# Humus_ethernet_dip_v1.net
KiCad netlist of a schematic drawn in EAGLE
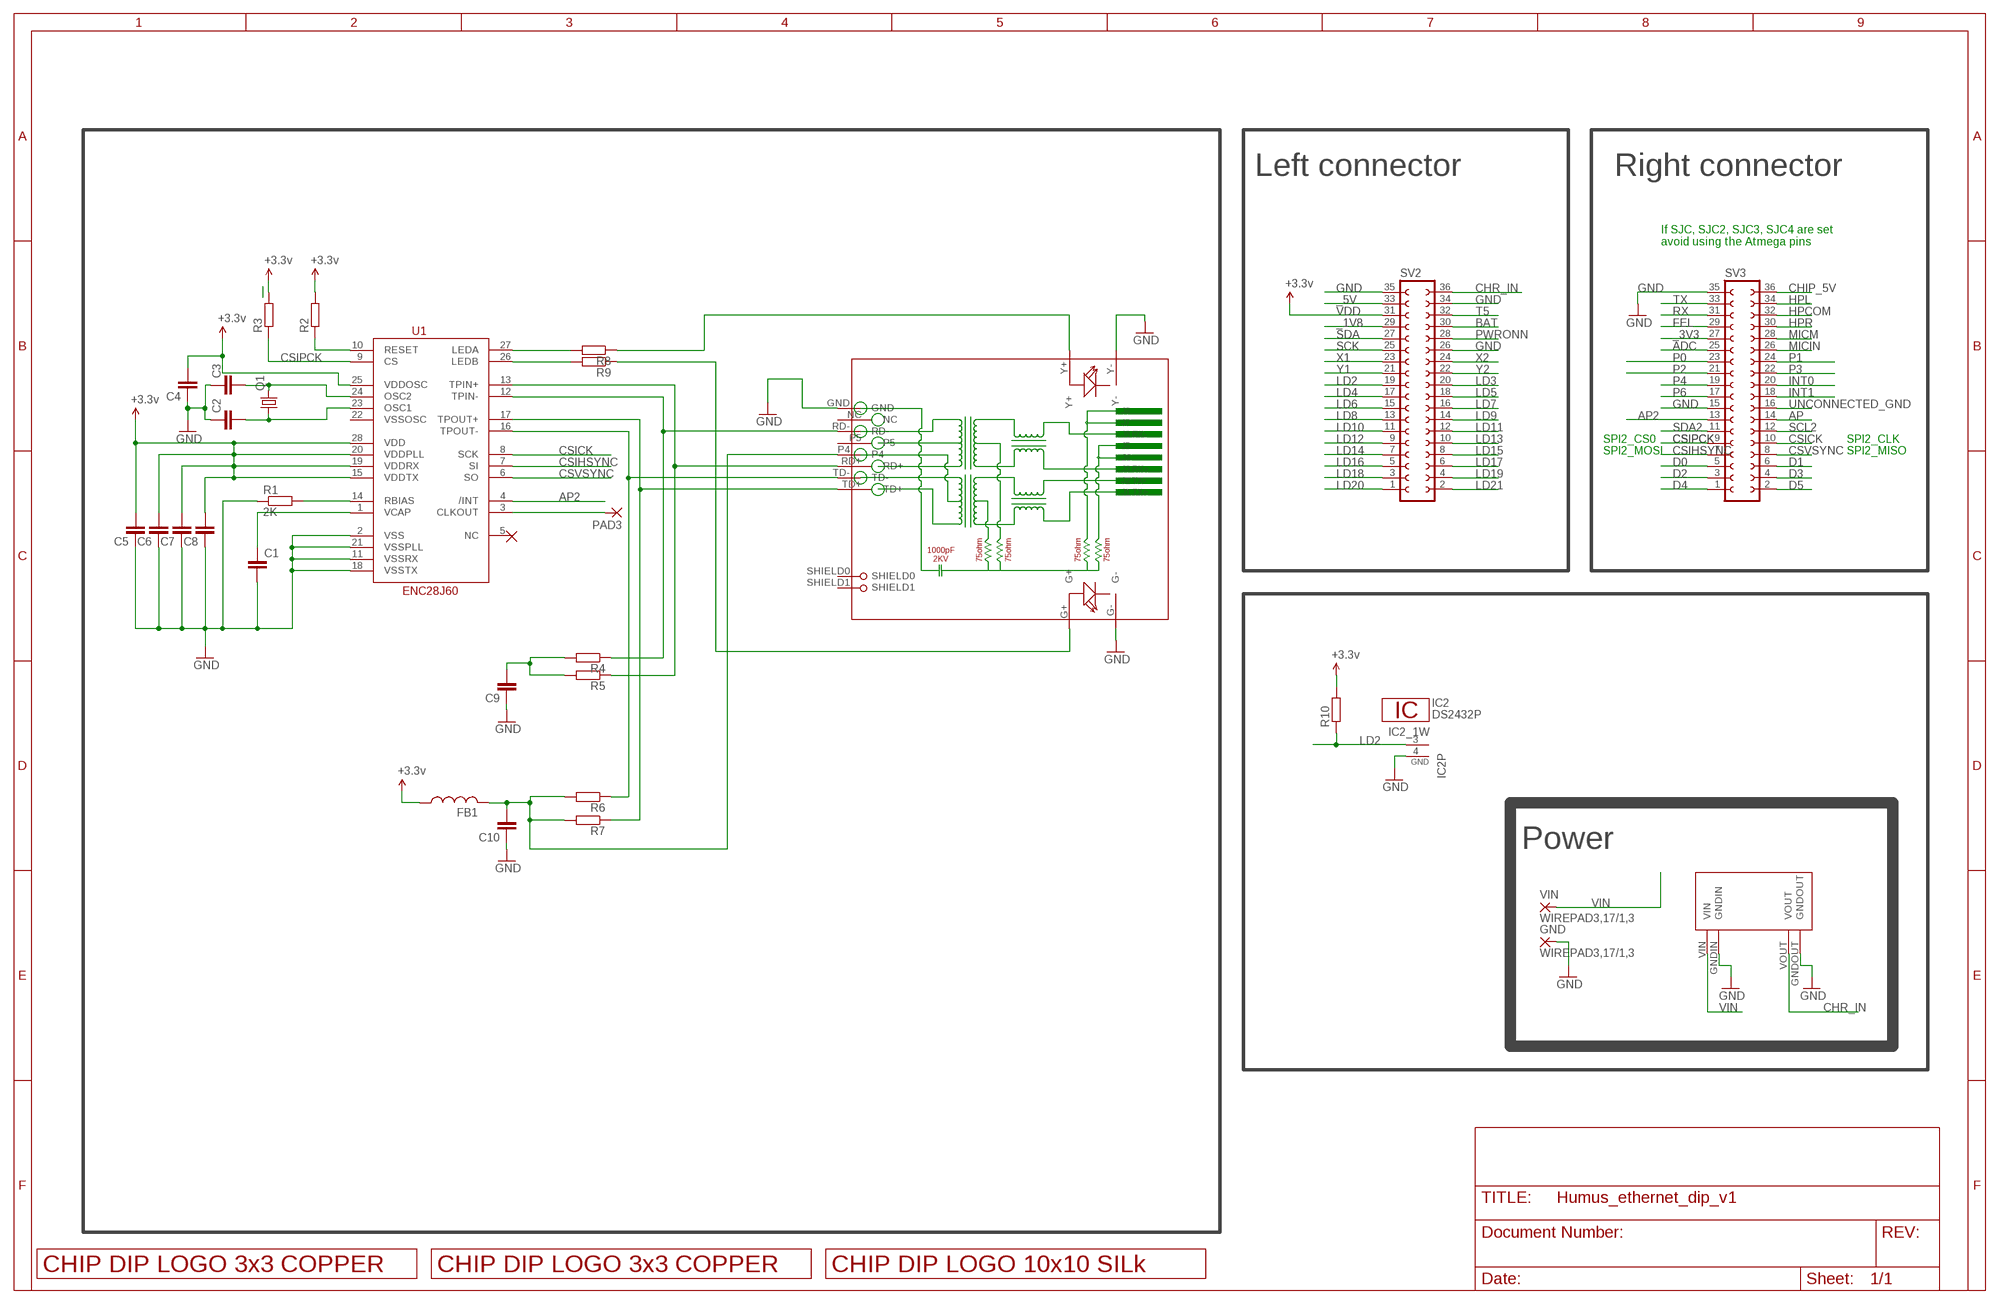
[diagram p0: schematic, sheet 1]

(export (version "E")
  (design (tool "Eeschema 10.0.6"))
  (components
    (comp (ref "C1")
      (value "C-EUC0805")
      (footprint "eagle-import:C0805")
      (libsource (lib "eagle-import") (part "C-EUC0805"))
    )
    (comp (ref "C2")
      (value "C-EUC0805")
      (footprint "eagle-import:C0805")
      (libsource (lib "eagle-import") (part "C-EUC0805"))
    )
    (comp (ref "C3")
      (value "C-EUC0805")
      (footprint "eagle-import:C0805")
      (libsource (lib "eagle-import") (part "C-EUC0805"))
    )
    (comp (ref "C4")
      (value "C-EUC0805")
      (footprint "eagle-import:C0805")
      (libsource (lib "eagle-import") (part "C-EUC0805"))
    )
    (comp (ref "C5")
      (value "C-EUC0805")
      (footprint "eagle-import:C0805")
      (libsource (lib "eagle-import") (part "C-EUC0805"))
    )
    (comp (ref "C6")
      (value "C-EUC0805")
      (footprint "eagle-import:C0805")
      (libsource (lib "eagle-import") (part "C-EUC0805"))
    )
    (comp (ref "C7")
      (value "C-EUC0805")
      (footprint "eagle-import:C0805")
      (libsource (lib "eagle-import") (part "C-EUC0805"))
    )
    (comp (ref "C8")
      (value "C-EUC0805")
      (footprint "eagle-import:C0805")
      (libsource (lib "eagle-import") (part "C-EUC0805"))
    )
    (comp (ref "C9")
      (value "C-EUC0805")
      (footprint "eagle-import:C0805")
      (libsource (lib "eagle-import") (part "C-EUC0805"))
    )
    (comp (ref "C10")
      (value "C-EUC0805")
      (footprint "eagle-import:C0805")
      (libsource (lib "eagle-import") (part "C-EUC0805"))
    )
    (comp (ref "FB1")
      (value "FERRITE-BEADB")
      (footprint "eagle-import:0805")
      (libsource (lib "eagle-import") (part "FERRITE-BEADB"))
    )
    (comp (ref "GND")
      (value "WIREPAD3,17/1,3")
      (footprint "eagle-import:3,17_1,3")
      (libsource (lib "eagle-import") (part "WIREPAD3,17/1,3"))
    )
    (comp (ref "IC2")
      (value "DS2432P")
      (footprint "eagle-import:TSOC6")
      (libsource (lib "eagle-import") (part "DS2432P"))
    )
    (comp (ref "PAD3")
      (value "WIREPADSMD1,27-254")
      (footprint "eagle-import:SMD1,27-2,54")
      (libsource (lib "eagle-import") (part "WIREPADSMD1,27-254"))
    )
    (comp (ref "Q1")
      (value "CRYSTALSM49")
      (footprint "eagle-import:SM49")
      (libsource (lib "eagle-import") (part "CRYSTALSM49"))
    )
    (comp (ref "R1")
      (value "2K")
      (footprint "eagle-import:R0805")
      (libsource (lib "eagle-import") (part "R-EU_R0805"))
    )
    (comp (ref "R2")
      (value "R-EU_R0805")
      (footprint "eagle-import:R0805")
      (libsource (lib "eagle-import") (part "R-EU_R0805"))
    )
    (comp (ref "R3")
      (value "R-EU_R0805")
      (footprint "eagle-import:R0805")
      (libsource (lib "eagle-import") (part "R-EU_R0805"))
    )
    (comp (ref "R4")
      (value "R-EU_R0805")
      (footprint "eagle-import:R0805")
      (libsource (lib "eagle-import") (part "R-EU_R0805"))
    )
    (comp (ref "R5")
      (value "R-EU_R0805")
      (footprint "eagle-import:R0805")
      (libsource (lib "eagle-import") (part "R-EU_R0805"))
    )
    (comp (ref "R6")
      (value "R-EU_R0805")
      (footprint "eagle-import:R0805")
      (libsource (lib "eagle-import") (part "R-EU_R0805"))
    )
    (comp (ref "R7")
      (value "R-EU_R0805")
      (footprint "eagle-import:R0805")
      (libsource (lib "eagle-import") (part "R-EU_R0805"))
    )
    (comp (ref "R8")
      (value "R-EU_R0805")
      (footprint "eagle-import:R0805")
      (libsource (lib "eagle-import") (part "R-EU_R0805"))
    )
    (comp (ref "R9")
      (value "R-EU_R0805")
      (footprint "eagle-import:R0805")
      (libsource (lib "eagle-import") (part "R-EU_R0805"))
    )
    (comp (ref "R10")
      (value "R-EU_R0805")
      (footprint "eagle-import:R0805")
      (libsource (lib "eagle-import") (part "R-EU_R0805"))
    )
    (comp (ref "RJ1")
      (value "HR911105A")
      (footprint "eagle-import:HR911105A")
      (libsource (lib "eagle-import") (part "HR911105A"))
    )
    (comp (ref "SV2")
      (value "FE18-2")
      (footprint "eagle-import:FE18-2")
      (libsource (lib "eagle-import") (part "FE18-2"))
    )
    (comp (ref "SV3")
      (value "FE18-2")
      (footprint "eagle-import:FE18-2")
      (libsource (lib "eagle-import") (part "FE18-2"))
    )
    (comp (ref "U$2")
      (value "LOGO_3X3_COPPER")
      (footprint "eagle-import:LOGO_3X3_COPPER")
      (libsource (lib "eagle-import") (part "LOGO_3X3_COPPER"))
    )
    (comp (ref "U$4")
      (value "LOGO_3X3_COPPER")
      (footprint "eagle-import:LOGO_3X3_COPPER")
      (libsource (lib "eagle-import") (part "LOGO_3X3_COPPER"))
    )
    (comp (ref "U$5")
      (value "LOGO_10X10_SILK")
      (footprint "eagle-import:LOGO_10X10_SILK")
      (libsource (lib "eagle-import") (part "LOGO_10X10_SILK"))
    )
    (comp (ref "U$9")
      (value "MP1584EN_FRAMELESS")
      (footprint "eagle-import:MP1584EN_FRAMELESS")
      (libsource (lib "eagle-import") (part "MP1584EN_FRAMELESS"))
    )
    (comp (ref "U1")
      (value "ENC28J60")
      (footprint "eagle-import:SSOP28DB")
      (libsource (lib "eagle-import") (part "ENC28J60"))
    )
    (comp (ref "VIN")
      (value "WIREPAD3,17/1,3")
      (footprint "eagle-import:3,17_1,3")
      (libsource (lib "eagle-import") (part "WIREPAD3,17/1,3"))
    )
  )
  (nets
    (net (code "1") (name "+3.3v") (class "Default")
      (node (ref "C4") (pin "2") (pinfunction "2_2") (pintype "passive"))
      (node (ref "C5") (pin "2") (pinfunction "2_2") (pintype "passive"))
      (node (ref "C6") (pin "2") (pinfunction "2_2") (pintype "passive"))
      (node (ref "C7") (pin "2") (pinfunction "2_2") (pintype "passive"))
      (node (ref "C8") (pin "2") (pinfunction "2_2") (pintype "passive"))
      (node (ref "FB1") (pin "1") (pinfunction "1_1") (pintype "passive"))
      (node (ref "R10") (pin "2") (pinfunction "2_2") (pintype "passive"))
      (node (ref "R2") (pin "2") (pinfunction "2_2") (pintype "passive"))
      (node (ref "R3") (pin "2") (pinfunction "2_2") (pintype "passive"))
      (node (ref "SV2") (pin "31") (pinfunction "31_31") (pintype "passive"))
      (node (ref "U1") (pin "15") (pinfunction "VDDTX_15") (pintype "bidirectional"))
      (node (ref "U1") (pin "19") (pinfunction "VDDRX_19") (pintype "bidirectional"))
      (node (ref "U1") (pin "20") (pinfunction "VDDPLL_20") (pintype "bidirectional"))
      (node (ref "U1") (pin "25") (pinfunction "VDDOSC_25") (pintype "bidirectional"))
      (node (ref "U1") (pin "28") (pinfunction "VDD_28") (pintype "bidirectional"))
    )
    (net (code "2") (name "/ADC") (class "Default")
      (node (ref "SV3") (pin "25") (pinfunction "25_25") (pintype "passive"))
    )
    (net (code "3") (name "/AP") (class "Default")
      (node (ref "SV3") (pin "14") (pinfunction "14_14") (pintype "passive"))
    )
    (net (code "4") (name "/AP2") (class "Default")
      (node (ref "SV3") (pin "13") (pinfunction "13_13") (pintype "passive"))
      (node (ref "U1") (pin "4") (pinfunction "/INT_4") (pintype "bidirectional"))
    )
    (net (code "5") (name "/BAT") (class "Default")
      (node (ref "SV2") (pin "30") (pinfunction "30_30") (pintype "passive"))
    )
    (net (code "6") (name "/CHIP_5V") (class "Default")
      (node (ref "SV3") (pin "36") (pinfunction "36_36") (pintype "passive"))
    )
    (net (code "7") (name "/CHR_IN") (class "Default")
      (node (ref "SV2") (pin "36") (pinfunction "36_36") (pintype "passive"))
      (node (ref "U$9") (pin "VOUT") (pinfunction "VOUT_VOUT") (pintype "power_in"))
    )
    (net (code "8") (name "/CSICK") (class "Default")
      (node (ref "SV3") (pin "10") (pinfunction "10_10") (pintype "passive"))
      (node (ref "U1") (pin "8") (pinfunction "SCK_8") (pintype "bidirectional"))
    )
    (net (code "9") (name "/CSIHSYNC") (class "Default")
      (node (ref "SV3") (pin "7") (pinfunction "7_7") (pintype "passive"))
      (node (ref "U1") (pin "7") (pinfunction "SI_7") (pintype "bidirectional"))
    )
    (net (code "10") (name "/CSIPCK") (class "Default")
      (node (ref "R3") (pin "1") (pinfunction "1_1") (pintype "passive"))
      (node (ref "SV3") (pin "9") (pinfunction "9_9") (pintype "passive"))
      (node (ref "U1") (pin "9") (pinfunction "CS_9") (pintype "bidirectional"))
    )
    (net (code "11") (name "/CSVSYNC") (class "Default")
      (node (ref "SV3") (pin "8") (pinfunction "8_8") (pintype "passive"))
      (node (ref "U1") (pin "6") (pinfunction "SO_6") (pintype "bidirectional"))
    )
    (net (code "12") (name "/D0") (class "Default")
      (node (ref "SV3") (pin "5") (pinfunction "5_5") (pintype "passive"))
    )
    (net (code "13") (name "/D1") (class "Default")
      (node (ref "SV3") (pin "6") (pinfunction "6_6") (pintype "passive"))
    )
    (net (code "14") (name "/D2") (class "Default")
      (node (ref "SV3") (pin "3") (pinfunction "3_3") (pintype "passive"))
    )
    (net (code "15") (name "/D3") (class "Default")
      (node (ref "SV3") (pin "4") (pinfunction "4_4") (pintype "passive"))
    )
    (net (code "16") (name "/D4") (class "Default")
      (node (ref "SV3") (pin "1") (pinfunction "1_1") (pintype "passive"))
    )
    (net (code "17") (name "/D5") (class "Default")
      (node (ref "SV3") (pin "2") (pinfunction "2_2") (pintype "passive"))
    )
    (net (code "18") (name "/FEL") (class "Default")
      (node (ref "SV3") (pin "29") (pinfunction "29_29") (pintype "passive"))
    )
    (net (code "19") (name "/HPCOM") (class "Default")
      (node (ref "SV3") (pin "32") (pinfunction "32_32") (pintype "passive"))
    )
    (net (code "20") (name "/HPL") (class "Default")
      (node (ref "SV3") (pin "34") (pinfunction "34_34") (pintype "passive"))
    )
    (net (code "21") (name "/HPR") (class "Default")
      (node (ref "SV3") (pin "30") (pinfunction "30_30") (pintype "passive"))
    )
    (net (code "22") (name "/INT0") (class "Default")
      (node (ref "SV3") (pin "20") (pinfunction "20_20") (pintype "passive"))
    )
    (net (code "23") (name "/INT1") (class "Default")
      (node (ref "SV3") (pin "18") (pinfunction "18_18") (pintype "passive"))
    )
    (net (code "24") (name "/LD2") (class "Default")
      (node (ref "IC2") (pin "3") (pinfunction "1W_3") (pintype "power_in"))
      (node (ref "R10") (pin "1") (pinfunction "1_1") (pintype "passive"))
      (node (ref "SV2") (pin "19") (pinfunction "19_19") (pintype "passive"))
    )
    (net (code "25") (name "/LD3") (class "Default")
      (node (ref "SV2") (pin "20") (pinfunction "20_20") (pintype "passive"))
    )
    (net (code "26") (name "/LD4") (class "Default")
      (node (ref "SV2") (pin "17") (pinfunction "17_17") (pintype "passive"))
    )
    (net (code "27") (name "/LD5") (class "Default")
      (node (ref "SV2") (pin "18") (pinfunction "18_18") (pintype "passive"))
    )
    (net (code "28") (name "/LD6") (class "Default")
      (node (ref "SV2") (pin "15") (pinfunction "15_15") (pintype "passive"))
    )
    (net (code "29") (name "/LD7") (class "Default")
      (node (ref "SV2") (pin "16") (pinfunction "16_16") (pintype "passive"))
    )
    (net (code "30") (name "/LD8") (class "Default")
      (node (ref "SV2") (pin "13") (pinfunction "13_13") (pintype "passive"))
    )
    (net (code "31") (name "/LD9") (class "Default")
      (node (ref "SV2") (pin "14") (pinfunction "14_14") (pintype "passive"))
    )
    (net (code "32") (name "/LD10") (class "Default")
      (node (ref "SV2") (pin "11") (pinfunction "11_11") (pintype "passive"))
    )
    (net (code "33") (name "/LD11") (class "Default")
      (node (ref "SV2") (pin "12") (pinfunction "12_12") (pintype "passive"))
    )
    (net (code "34") (name "/LD12") (class "Default")
      (node (ref "SV2") (pin "9") (pinfunction "9_9") (pintype "passive"))
    )
    (net (code "35") (name "/LD13") (class "Default")
      (node (ref "SV2") (pin "10") (pinfunction "10_10") (pintype "passive"))
    )
    (net (code "36") (name "/LD14") (class "Default")
      (node (ref "SV2") (pin "7") (pinfunction "7_7") (pintype "passive"))
    )
    (net (code "37") (name "/LD15") (class "Default")
      (node (ref "SV2") (pin "8") (pinfunction "8_8") (pintype "passive"))
    )
    (net (code "38") (name "/LD16") (class "Default")
      (node (ref "SV2") (pin "5") (pinfunction "5_5") (pintype "passive"))
    )
    (net (code "39") (name "/LD17") (class "Default")
      (node (ref "SV2") (pin "6") (pinfunction "6_6") (pintype "passive"))
    )
    (net (code "40") (name "/LD18") (class "Default")
      (node (ref "SV2") (pin "3") (pinfunction "3_3") (pintype "passive"))
    )
    (net (code "41") (name "/LD19") (class "Default")
      (node (ref "SV2") (pin "4") (pinfunction "4_4") (pintype "passive"))
    )
    (net (code "42") (name "/LD20") (class "Default")
      (node (ref "SV2") (pin "1") (pinfunction "1_1") (pintype "passive"))
    )
    (net (code "43") (name "/LD21") (class "Default")
      (node (ref "SV2") (pin "2") (pinfunction "2_2") (pintype "passive"))
    )
    (net (code "44") (name "/MICIN") (class "Default")
      (node (ref "SV3") (pin "26") (pinfunction "26_26") (pintype "passive"))
    )
    (net (code "45") (name "/MICM") (class "Default")
      (node (ref "SV3") (pin "28") (pinfunction "28_28") (pintype "passive"))
    )
    (net (code "46") (name "/P0") (class "Default")
      (node (ref "SV3") (pin "23") (pinfunction "23_23") (pintype "passive"))
    )
    (net (code "47") (name "/P1") (class "Default")
      (node (ref "SV3") (pin "24") (pinfunction "24_24") (pintype "passive"))
    )
    (net (code "48") (name "/P2") (class "Default")
      (node (ref "SV3") (pin "21") (pinfunction "21_21") (pintype "passive"))
    )
    (net (code "49") (name "/P3") (class "Default")
      (node (ref "SV3") (pin "22") (pinfunction "22_22") (pintype "passive"))
    )
    (net (code "50") (name "/P4") (class "Default")
      (node (ref "SV3") (pin "19") (pinfunction "19_19") (pintype "passive"))
    )
    (net (code "51") (name "/P6") (class "Default")
      (node (ref "SV3") (pin "17") (pinfunction "17_17") (pintype "passive"))
    )
    (net (code "52") (name "/PWRONN") (class "Default")
      (node (ref "SV2") (pin "28") (pinfunction "28_28") (pintype "passive"))
    )
    (net (code "53") (name "/RX") (class "Default")
      (node (ref "SV3") (pin "31") (pinfunction "31_31") (pintype "passive"))
    )
    (net (code "54") (name "/SCK") (class "Default")
      (node (ref "SV2") (pin "25") (pinfunction "25_25") (pintype "passive"))
    )
    (net (code "55") (name "/SCL2") (class "Default")
      (node (ref "SV3") (pin "12") (pinfunction "12_12") (pintype "passive"))
    )
    (net (code "56") (name "/SDA") (class "Default")
      (node (ref "SV2") (pin "27") (pinfunction "27_27") (pintype "passive"))
    )
    (net (code "57") (name "/SDA2") (class "Default")
      (node (ref "SV3") (pin "11") (pinfunction "11_11") (pintype "passive"))
    )
    (net (code "58") (name "/T5") (class "Default")
      (node (ref "SV2") (pin "32") (pinfunction "32_32") (pintype "passive"))
    )
    (net (code "59") (name "/TX") (class "Default")
      (node (ref "SV3") (pin "33") (pinfunction "33_33") (pintype "passive"))
    )
    (net (code "60") (name "/UNCONNECTED_GND") (class "Default")
      (node (ref "SV3") (pin "16") (pinfunction "16_16") (pintype "passive"))
    )
    (net (code "61") (name "/VIN") (class "Default")
      (node (ref "U$9") (pin "VIN") (pinfunction "VIN_VIN") (pintype "power_in"))
      (node (ref "VIN") (pin "1") (pinfunction "P_1") (pintype "passive"))
    )
    (net (code "62") (name "/X1") (class "Default")
      (node (ref "SV2") (pin "23") (pinfunction "23_23") (pintype "passive"))
    )
    (net (code "63") (name "/X2") (class "Default")
      (node (ref "SV2") (pin "24") (pinfunction "24_24") (pintype "passive"))
    )
    (net (code "64") (name "/Y1") (class "Default")
      (node (ref "SV2") (pin "21") (pinfunction "21_21") (pintype "passive"))
    )
    (net (code "65") (name "/Y2") (class "Default")
      (node (ref "SV2") (pin "22") (pinfunction "22_22") (pintype "passive"))
    )
    (net (code "66") (name "/_1V8") (class "Default")
      (node (ref "SV2") (pin "29") (pinfunction "29_29") (pintype "passive"))
    )
    (net (code "67") (name "/_3V3") (class "Default")
      (node (ref "SV3") (pin "27") (pinfunction "27_27") (pintype "passive"))
    )
    (net (code "68") (name "/_5V") (class "Default")
      (node (ref "SV2") (pin "33") (pinfunction "33_33") (pintype "passive"))
    )
    (net (code "69") (name "GND") (class "Default")
      (node (ref "C1") (pin "2") (pinfunction "2_2") (pintype "passive"))
      (node (ref "C10") (pin "1") (pinfunction "1_1") (pintype "passive"))
      (node (ref "C2") (pin "1") (pinfunction "1_1") (pintype "passive"))
      (node (ref "C3") (pin "1") (pinfunction "1_1") (pintype "passive"))
      (node (ref "C4") (pin "1") (pinfunction "1_1") (pintype "passive"))
      (node (ref "C5") (pin "1") (pinfunction "1_1") (pintype "passive"))
      (node (ref "C6") (pin "1") (pinfunction "1_1") (pintype "passive"))
      (node (ref "C7") (pin "1") (pinfunction "1_1") (pintype "passive"))
      (node (ref "C8") (pin "1") (pinfunction "1_1") (pintype "passive"))
      (node (ref "C9") (pin "1") (pinfunction "1_1") (pintype "passive"))
      (node (ref "GND") (pin "1") (pinfunction "P_1") (pintype "passive"))
      (node (ref "IC2") (pin "4") (pinfunction "GND_4") (pintype "power_in"))
      (node (ref "R1") (pin "1") (pinfunction "1_1") (pintype "passive"))
      (node (ref "RJ1") (pin "G-") (pinfunction "G-_G-") (pintype "bidirectional"))
      (node (ref "RJ1") (pin "GND") (pinfunction "GND_GND") (pintype "bidirectional"))
      (node (ref "RJ1") (pin "Y-") (pinfunction "Y-_Y-") (pintype "bidirectional"))
      (node (ref "SV2") (pin "26") (pinfunction "26_26") (pintype "passive"))
      (node (ref "SV2") (pin "34") (pinfunction "34_34") (pintype "passive"))
      (node (ref "SV2") (pin "35") (pinfunction "35_35") (pintype "passive"))
      (node (ref "SV3") (pin "15") (pinfunction "15_15") (pintype "passive"))
      (node (ref "SV3") (pin "35") (pinfunction "35_35") (pintype "passive"))
      (node (ref "U$9") (pin "GNDIN") (pinfunction "GNDIN_GNDIN") (pintype "power_in"))
      (node (ref "U$9") (pin "GNDOUT") (pinfunction "GNDOUT_GNDOUT") (pintype "power_in"))
      (node (ref "U1") (pin "11") (pinfunction "VSSRX_11") (pintype "bidirectional"))
      (node (ref "U1") (pin "18") (pinfunction "VSSTX_18") (pintype "bidirectional"))
      (node (ref "U1") (pin "2") (pinfunction "VSS_2") (pintype "bidirectional"))
      (node (ref "U1") (pin "21") (pinfunction "VSSPLL_21") (pintype "bidirectional"))
    )
    (net (code "70") (name "Net-(C9-Pad2)") (class "Default")
      (node (ref "C9") (pin "2") (pinfunction "2_2") (pintype "passive"))
      (node (ref "R4") (pin "2") (pinfunction "2_2") (pintype "passive"))
      (node (ref "R5") (pin "2") (pinfunction "2_2") (pintype "passive"))
    )
    (net (code "71") (name "Net-(C10-Pad2)") (class "Default")
      (node (ref "C10") (pin "2") (pinfunction "2_2") (pintype "passive"))
      (node (ref "FB1") (pin "2") (pinfunction "2_2") (pintype "passive"))
      (node (ref "R6") (pin "2") (pinfunction "2_2") (pintype "passive"))
      (node (ref "R7") (pin "2") (pinfunction "2_2") (pintype "passive"))
      (node (ref "RJ1") (pin "P4") (pinfunction "P4_P4") (pintype "bidirectional"))
    )
    (net (code "72") (name "Net-(PAD3-P)") (class "Default")
      (node (ref "PAD3") (pin "1") (pinfunction "P_1") (pintype "passive"))
      (node (ref "U1") (pin "3") (pinfunction "CLKOUT_3") (pintype "bidirectional"))
    )
    (net (code "73") (name "Net-(R8-Pad1)") (class "Default")
      (node (ref "R8") (pin "1") (pinfunction "1_1") (pintype "passive"))
      (node (ref "RJ1") (pin "Y+") (pinfunction "Y+_Y+") (pintype "bidirectional"))
    )
    (net (code "74") (name "Net-(R9-Pad1)") (class "Default")
      (node (ref "R9") (pin "1") (pinfunction "1_1") (pintype "passive"))
      (node (ref "RJ1") (pin "G+") (pinfunction "G+_G+") (pintype "bidirectional"))
    )
    (net (code "75") (name "Net-(U1-LEDA)") (class "Default")
      (node (ref "R8") (pin "2") (pinfunction "2_2") (pintype "passive"))
      (node (ref "U1") (pin "27") (pinfunction "LEDA_27") (pintype "bidirectional"))
    )
    (net (code "76") (name "Net-(U1-LEDB)") (class "Default")
      (node (ref "R9") (pin "2") (pinfunction "2_2") (pintype "passive"))
      (node (ref "U1") (pin "26") (pinfunction "LEDB_26") (pintype "bidirectional"))
    )
    (net (code "77") (name "Net-(U1-OSC1)") (class "Default")
      (node (ref "C2") (pin "2") (pinfunction "2_2") (pintype "passive"))
      (node (ref "Q1") (pin "1") (pinfunction "1_1") (pintype "passive"))
      (node (ref "U1") (pin "23") (pinfunction "OSC1_23") (pintype "bidirectional"))
    )
    (net (code "78") (name "Net-(U1-OSC2)") (class "Default")
      (node (ref "C3") (pin "2") (pinfunction "2_2") (pintype "passive"))
      (node (ref "Q1") (pin "2") (pinfunction "2_2") (pintype "passive"))
      (node (ref "U1") (pin "24") (pinfunction "OSC2_24") (pintype "bidirectional"))
    )
    (net (code "79") (name "Net-(U1-RBIAS)") (class "Default")
      (node (ref "R1") (pin "2") (pinfunction "2_2") (pintype "passive"))
      (node (ref "U1") (pin "14") (pinfunction "RBIAS_14") (pintype "bidirectional"))
    )
    (net (code "80") (name "Net-(U1-RESET)") (class "Default")
      (node (ref "R2") (pin "1") (pinfunction "1_1") (pintype "passive"))
      (node (ref "U1") (pin "10") (pinfunction "RESET_10") (pintype "bidirectional"))
    )
    (net (code "81") (name "Net-(U1-TPIN+)") (class "Default")
      (node (ref "R5") (pin "1") (pinfunction "1_1") (pintype "passive"))
      (node (ref "RJ1") (pin "RD+") (pinfunction "RD+_RD+") (pintype "bidirectional"))
      (node (ref "U1") (pin "13") (pinfunction "TPIN+_13") (pintype "bidirectional"))
    )
    (net (code "82") (name "Net-(U1-TPIN-)") (class "Default")
      (node (ref "R4") (pin "1") (pinfunction "1_1") (pintype "passive"))
      (node (ref "RJ1") (pin "RD-") (pinfunction "RD-_RD-") (pintype "bidirectional"))
      (node (ref "U1") (pin "12") (pinfunction "TPIN-_12") (pintype "bidirectional"))
    )
    (net (code "83") (name "Net-(U1-TPOUT+)") (class "Default")
      (node (ref "R7") (pin "1") (pinfunction "1_1") (pintype "passive"))
      (node (ref "RJ1") (pin "TD+") (pinfunction "TD+_TD+") (pintype "bidirectional"))
      (node (ref "U1") (pin "17") (pinfunction "TPOUT+_17") (pintype "bidirectional"))
    )
    (net (code "84") (name "Net-(U1-TPOUT-)") (class "Default")
      (node (ref "R6") (pin "1") (pinfunction "1_1") (pintype "passive"))
      (node (ref "RJ1") (pin "TD-") (pinfunction "TD-_TD-") (pintype "bidirectional"))
      (node (ref "U1") (pin "16") (pinfunction "TPOUT-_16") (pintype "bidirectional"))
    )
    (net (code "85") (name "Net-(U1-VCAP)") (class "Default")
      (node (ref "C1") (pin "1") (pinfunction "1_1") (pintype "passive"))
      (node (ref "U1") (pin "1") (pinfunction "VCAP_1") (pintype "bidirectional"))
    )
    (net (code "86") (name "unconnected-(RJ1-PadNC)") (class "Default")
      (node (ref "RJ1") (pin "NC") (pinfunction "NC_NC") (pintype "bidirectional"))
    )
    (net (code "87") (name "unconnected-(RJ1-PadP5)") (class "Default")
      (node (ref "RJ1") (pin "P5") (pinfunction "P5_P5") (pintype "bidirectional"))
    )
    (net (code "88") (name "unconnected-(RJ1-PadSHIELD0)") (class "Default")
      (node (ref "RJ1") (pin "SHIELD0") (pinfunction "SHIELD0_SHIELD0") (pintype "bidirectional"))
    )
    (net (code "89") (name "unconnected-(RJ1-PadSHIELD1)") (class "Default")
      (node (ref "RJ1") (pin "SHIELD1") (pinfunction "SHIELD1_SHIELD1") (pintype "bidirectional"))
    )
    (net (code "90") (name "unconnected-(U1-NC-Pad5)") (class "Default")
      (node (ref "U1") (pin "5") (pinfunction "NC_5") (pintype "bidirectional"))
    )
    (net (code "91") (name "unconnected-(U1-VSSOSC-Pad22)") (class "Default")
      (node (ref "U1") (pin "22") (pinfunction "VSSOSC_22") (pintype "bidirectional"))
    )
  )
)
